# Sheet1.net
KiCad netlist of a schematic drawn in Altium Designer
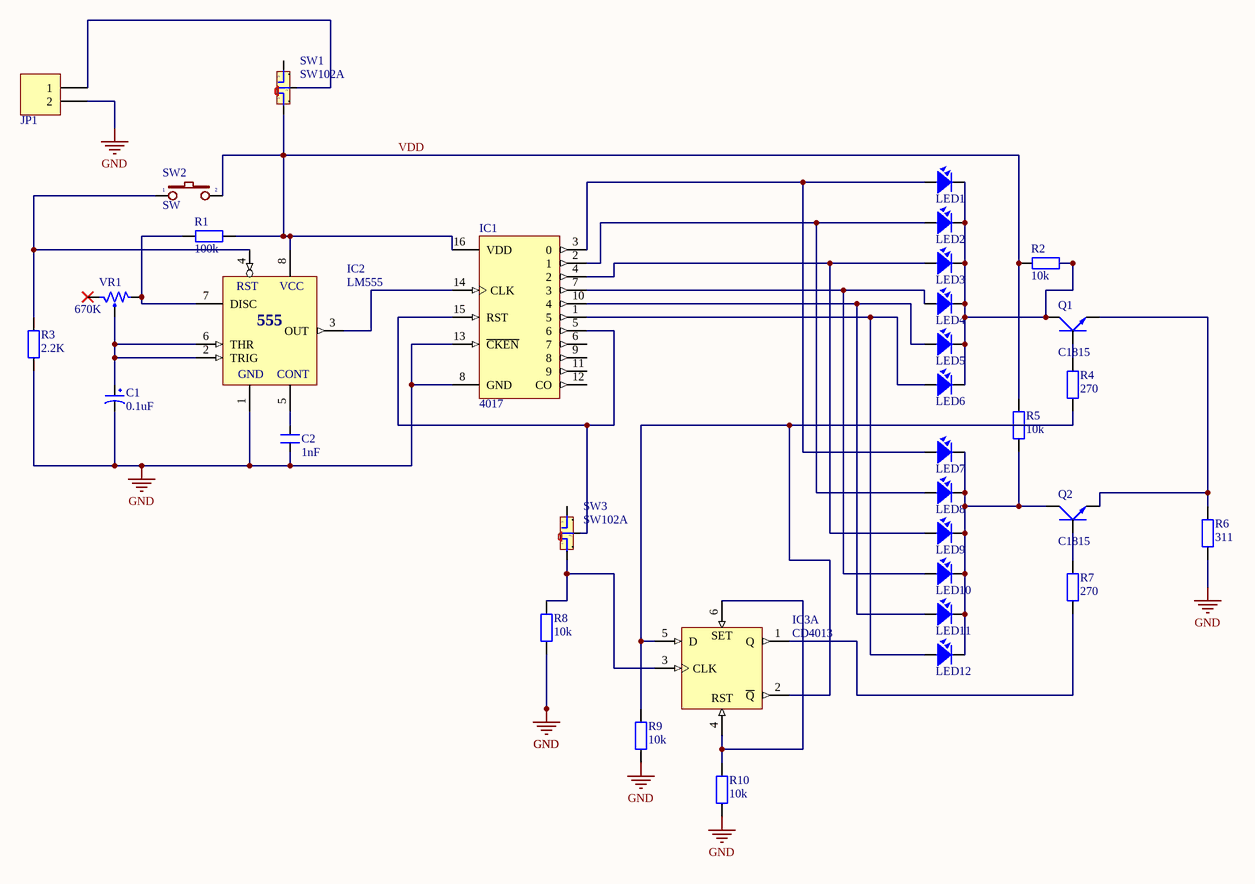
[diagram p0: Sheet1.SchDoc]

(export (version "E")
  (design (tool "Eeschema 10.0.6"))
  (components
    (comp (ref "C1")
      (value "0.1uF")
      (footprint "CP1/2")
      (description "Cap P  0,1uF < 22uF , 16 - 50V")
      (libsource (lib "syhaunguyen") (part "CP1"))
    )
    (comp (ref "C2")
      (value "1nF")
      (footprint "CN1.5")
      (description "Cap np 682pF => 104pF")
      (libsource (lib "syhaunguyen") (part "CN1.5"))
    )
    (comp (ref "IC1")
      (value "4017")
      (footprint "Dip16/w0.3")
      (description "Decade Counter/Divider with 10 Decoded Outputs")
      (fields (field (name "DESIGNED BY") "VanDungEvn"))
      (libsource (lib "My library altium") (part "4017"))
    )
    (comp (ref "IC2")
      (value "LM555")
      (footprint "DIP8/W0.3")
      (description "Timer")
      (libsource (lib "My library altium") (part "LM555"))
    )
    (comp (ref "IC3")
      (value "CD4013")
      (footprint "DIP14/W0.3")
      (description "Dual D-Type Flip-Flop")
      (fields (field (name "CREAT BY") "VanDungEvn@Gmail.com"))
      (libsource (lib "syhaunguyen") (part "CD4013B"))
    )
    (comp (ref "JP1")
      (value "Header 2_1")
      (footprint "HED2")
      (description "Header, 2-Pin")
      (fields (field (name "MANUFACTURER") "Generic Components"))
      (libsource (lib "syhaunguyen") (part "Header 2_1"))
    )
    (comp (ref "LED1")
      (value "LED")
      (footprint "LED-5-RED")
      (description "LED Single colour Green and Red")
      (libsource (lib "syhaunguyen") (part "LED"))
    )
    (comp (ref "LED2")
      (value "LED")
      (footprint "LED-5-RED")
      (description "LED Single colour Green and Red")
      (libsource (lib "syhaunguyen") (part "LED"))
    )
    (comp (ref "LED3")
      (value "LED")
      (footprint "LED-5-RED")
      (description "LED Single colour Green and Red")
      (libsource (lib "syhaunguyen") (part "LED"))
    )
    (comp (ref "LED4")
      (value "LED")
      (footprint "LED-5-RED")
      (description "LED Single colour Green and Red")
      (libsource (lib "syhaunguyen") (part "LED"))
    )
    (comp (ref "LED5")
      (value "LED")
      (footprint "LED-5-RED")
      (description "LED Single colour Green and Red")
      (libsource (lib "syhaunguyen") (part "LED"))
    )
    (comp (ref "LED6")
      (value "LED")
      (footprint "LED-5-RED")
      (description "LED Single colour Green and Red")
      (libsource (lib "syhaunguyen") (part "LED"))
    )
    (comp (ref "LED7")
      (value "LED")
      (footprint "LED-5-RED")
      (description "LED Single colour Green and Red")
      (libsource (lib "syhaunguyen") (part "LED"))
    )
    (comp (ref "LED8")
      (value "LED")
      (footprint "LED-5-RED")
      (description "LED Single colour Green and Red")
      (libsource (lib "syhaunguyen") (part "LED"))
    )
    (comp (ref "LED9")
      (value "LED")
      (footprint "LED-5-RED")
      (description "LED Single colour Green and Red")
      (libsource (lib "syhaunguyen") (part "LED"))
    )
    (comp (ref "LED10")
      (value "LED")
      (footprint "LED-5-RED")
      (description "LED Single colour Green and Red")
      (libsource (lib "syhaunguyen") (part "LED"))
    )
    (comp (ref "LED11")
      (value "LED")
      (footprint "LED-5-RED")
      (description "LED Single colour Green and Red")
      (libsource (lib "syhaunguyen") (part "LED"))
    )
    (comp (ref "LED12")
      (value "LED")
      (footprint "LED-5-RED")
      (description "LED Single colour Green and Red")
      (libsource (lib "syhaunguyen") (part "LED"))
    )
    (comp (ref "Q1")
      (value "C1815")
      (footprint "QTO-92")
      (description "NPN 600mW, ECB")
      (libsource (lib "syhaunguyen") (part "C1815"))
    )
    (comp (ref "Q2")
      (value "C1815")
      (footprint "QTO-92")
      (description "NPN 600mW, ECB")
      (libsource (lib "syhaunguyen") (part "C1815"))
    )
    (comp (ref "R1")
      (value "100k")
      (footprint "R1/4W")
      (description "Resistor 1/4W")
      (libsource (lib "syhaunguyen") (part "R1/4W"))
    )
    (comp (ref "R2")
      (value "10k")
      (footprint "R1/4W")
      (description "Resistor 1/4W")
      (libsource (lib "syhaunguyen") (part "R1/4W"))
    )
    (comp (ref "R3")
      (value "2.2K")
      (footprint "R1/4W")
      (description "Resistor 1/4W")
      (libsource (lib "syhaunguyen") (part "R1/4W"))
    )
    (comp (ref "R4")
      (value "270")
      (footprint "R1/4W")
      (description "Resistor 1/4W")
      (libsource (lib "syhaunguyen") (part "R1/4W"))
    )
    (comp (ref "R5")
      (value "10k")
      (footprint "R1/4W")
      (description "Resistor 1/4W")
      (libsource (lib "syhaunguyen") (part "R1/4W"))
    )
    (comp (ref "R6")
      (value "311")
      (footprint "R1/4W")
      (description "Resistor 1/4W")
      (libsource (lib "syhaunguyen") (part "R1/4W"))
    )
    (comp (ref "R7")
      (value "270")
      (footprint "R1/4W")
      (description "Resistor 1/4W")
      (libsource (lib "syhaunguyen") (part "R1/4W"))
    )
    (comp (ref "R8")
      (value "10k")
      (footprint "R1/4W")
      (description "Resistor 1/4W")
      (libsource (lib "syhaunguyen") (part "R1/4W"))
    )
    (comp (ref "R9")
      (value "10k")
      (footprint "R1/4W")
      (description "Resistor 1/4W")
      (libsource (lib "syhaunguyen") (part "R1/4W"))
    )
    (comp (ref "R10")
      (value "10k")
      (footprint "R1/4W")
      (description "Resistor 1/4W")
      (libsource (lib "syhaunguyen") (part "R1/4W"))
    )
    (comp (ref "SW1")
      (value "SW102A")
      (footprint "SW102")
      (description "Switch 102 on Broad")
      (libsource (lib "My library altium") (part "SW102A"))
    )
    (comp (ref "SW2")
      (value "SW")
      (footprint "SW2")
      (description "Switch button 2 pin")
      (libsource (lib "syhaunguyen") (part "SW2"))
    )
    (comp (ref "SW3")
      (value "SW102A")
      (footprint "SW102")
      (description "Switch 102 on Broad")
      (libsource (lib "My library altium") (part "SW102A"))
    )
    (comp (ref "VR1")
      (value "670K")
      (footprint "VR")
      (description "Var Resistor")
      (libsource (lib "syhaunguyen") (part "VR1"))
    )
  )
  (nets
    (net (code "1") (name "GND") (class "Default")
      (node (ref "C1") (pin "2") (pinfunction "2_2") (pintype "passive"))
      (node (ref "C2") (pin "1") (pinfunction "1_1") (pintype "passive"))
      (node (ref "IC1") (pin "13") (pinfunction "~{CKEN}_13") (pintype "input"))
      (node (ref "IC1") (pin "8") (pinfunction "GND_8") (pintype "power_in"))
      (node (ref "IC2") (pin "1") (pinfunction "GND_1") (pintype "power_in"))
      (node (ref "IC3") (pin "7") (pinfunction "GND_7") (pintype "power_in"))
      (node (ref "JP1") (pin "2") (pinfunction "2_2") (pintype "passive"))
      (node (ref "R10") (pin "1") (pinfunction "1_1") (pintype "passive"))
      (node (ref "R3") (pin "1") (pinfunction "1_1") (pintype "passive"))
      (node (ref "R6") (pin "2") (pinfunction "2_2") (pintype "passive"))
      (node (ref "R8") (pin "2") (pinfunction "2_2") (pintype "passive"))
      (node (ref "R9") (pin "1") (pinfunction "1_1") (pintype "passive"))
    )
    (net (code "2") (name "Net-(IC1-0)") (class "Default")
      (node (ref "IC1") (pin "3") (pinfunction "0_3") (pintype "output"))
      (node (ref "LED1") (pin "1") (pinfunction "1_1") (pintype "passive"))
      (node (ref "LED7") (pin "1") (pinfunction "1_1") (pintype "passive"))
    )
    (net (code "3") (name "Net-(IC1-1)") (class "Default")
      (node (ref "IC1") (pin "2") (pinfunction "1_2") (pintype "output"))
      (node (ref "LED2") (pin "1") (pinfunction "1_1") (pintype "passive"))
      (node (ref "LED8") (pin "1") (pinfunction "1_1") (pintype "passive"))
    )
    (net (code "4") (name "Net-(IC1-2)") (class "Default")
      (node (ref "IC1") (pin "4") (pinfunction "2_4") (pintype "output"))
      (node (ref "LED3") (pin "1") (pinfunction "1_1") (pintype "passive"))
      (node (ref "LED9") (pin "1") (pinfunction "1_1") (pintype "passive"))
    )
    (net (code "5") (name "Net-(IC1-3)") (class "Default")
      (node (ref "IC1") (pin "7") (pinfunction "3_7") (pintype "output"))
      (node (ref "LED10") (pin "1") (pinfunction "1_1") (pintype "passive"))
      (node (ref "LED4") (pin "1") (pinfunction "1_1") (pintype "passive"))
    )
    (net (code "6") (name "Net-(IC1-4)") (class "Default")
      (node (ref "IC1") (pin "10") (pinfunction "4_10") (pintype "output"))
      (node (ref "LED11") (pin "1") (pinfunction "1_1") (pintype "passive"))
      (node (ref "LED5") (pin "1") (pinfunction "1_1") (pintype "passive"))
    )
    (net (code "7") (name "Net-(IC1-5)") (class "Default")
      (node (ref "IC1") (pin "1") (pinfunction "5_1") (pintype "output"))
      (node (ref "LED12") (pin "1") (pinfunction "1_1") (pintype "passive"))
      (node (ref "LED6") (pin "1") (pinfunction "1_1") (pintype "passive"))
    )
    (net (code "8") (name "Net-(IC1-6)") (class "Default")
      (node (ref "IC1") (pin "15") (pinfunction "RST_15") (pintype "input"))
      (node (ref "IC1") (pin "5") (pinfunction "6_5") (pintype "output"))
      (node (ref "SW3") (pin "2") (pinfunction "2_2") (pintype "passive"))
    )
    (net (code "9") (name "Net-(IC1-CLK)") (class "Default")
      (node (ref "IC1") (pin "14") (pinfunction "CLK_14") (pintype "input"))
      (node (ref "IC2") (pin "3") (pinfunction "OUT_3") (pintype "output"))
    )
    (net (code "10") (name "Net-(IC2-CONT)") (class "Default")
      (node (ref "C2") (pin "2") (pinfunction "2_2") (pintype "passive"))
      (node (ref "IC2") (pin "5") (pinfunction "CONT_5") (pintype "passive"))
    )
    (net (code "11") (name "Net-(IC2-DISC)") (class "Default")
      (node (ref "IC2") (pin "7") (pinfunction "DISC_7") (pintype "open_collector"))
      (node (ref "R1") (pin "2") (pinfunction "2_2") (pintype "passive"))
      (node (ref "VR1") (pin "1") (pinfunction "1_1") (pintype "passive"))
    )
    (net (code "12") (name "Net-(IC2-RST)") (class "Default")
      (node (ref "IC2") (pin "4") (pinfunction "RST_4") (pintype "input"))
      (node (ref "R3") (pin "2") (pinfunction "2_2") (pintype "passive"))
      (node (ref "SW2") (pin "1") (pinfunction "1_1") (pintype "passive"))
    )
    (net (code "13") (name "Net-(IC2-THR)") (class "Default")
      (node (ref "C1") (pin "1") (pinfunction "1_1") (pintype "passive"))
      (node (ref "IC2") (pin "2") (pinfunction "TRIG_2") (pintype "input"))
      (node (ref "IC2") (pin "6") (pinfunction "THR_6") (pintype "input"))
      (node (ref "VR1") (pin "2") (pinfunction "2_2") (pintype "passive"))
    )
    (net (code "14") (name "Net-(IC3A-CLK)") (class "Default")
      (node (ref "IC3") (pin "3") (pinfunction "CLK_3") (pintype "input"))
      (node (ref "R8") (pin "1") (pinfunction "1_1") (pintype "passive"))
      (node (ref "SW3") (pin "1") (pinfunction "1_1") (pintype "passive"))
    )
    (net (code "15") (name "Net-(IC3A-D)") (class "Default")
      (node (ref "IC3") (pin "2") (pinfunction "~{Q}_2") (pintype "output"))
      (node (ref "IC3") (pin "5") (pinfunction "D_5") (pintype "input"))
      (node (ref "R4") (pin "2") (pinfunction "2_2") (pintype "passive"))
      (node (ref "R9") (pin "2") (pinfunction "2_2") (pintype "passive"))
    )
    (net (code "16") (name "Net-(IC3A-Q)") (class "Default")
      (node (ref "IC3") (pin "1") (pinfunction "Q_1") (pintype "output"))
      (node (ref "R7") (pin "1") (pinfunction "1_1") (pintype "passive"))
    )
    (net (code "17") (name "Net-(IC3A-RST)") (class "Default")
      (node (ref "IC3") (pin "4") (pinfunction "RST_4") (pintype "input"))
      (node (ref "IC3") (pin "6") (pinfunction "S_6") (pintype "input"))
      (node (ref "R10") (pin "2") (pinfunction "2_2") (pintype "passive"))
    )
    (net (code "18") (name "Net-(JP1-Pad1)") (class "Default")
      (node (ref "JP1") (pin "1") (pinfunction "1_1") (pintype "passive"))
      (node (ref "SW1") (pin "2") (pinfunction "2_2") (pintype "passive"))
    )
    (net (code "19") (name "Net-(Q1-B)") (class "Default")
      (node (ref "Q1") (pin "3") (pinfunction "B_3") (pintype "passive"))
      (node (ref "R4") (pin "1") (pinfunction "1_1") (pintype "passive"))
    )
    (net (code "20") (name "Net-(Q1-C)") (class "Default")
      (node (ref "LED1") (pin "2") (pinfunction "2_2") (pintype "passive"))
      (node (ref "LED2") (pin "2") (pinfunction "2_2") (pintype "passive"))
      (node (ref "LED3") (pin "2") (pinfunction "2_2") (pintype "passive"))
      (node (ref "LED4") (pin "2") (pinfunction "2_2") (pintype "passive"))
      (node (ref "LED5") (pin "2") (pinfunction "2_2") (pintype "passive"))
      (node (ref "LED6") (pin "2") (pinfunction "2_2") (pintype "passive"))
      (node (ref "Q1") (pin "2") (pinfunction "C_2") (pintype "passive"))
      (node (ref "R2") (pin "1") (pinfunction "1_1") (pintype "passive"))
    )
    (net (code "21") (name "Net-(Q1-E)") (class "Default")
      (node (ref "Q1") (pin "1") (pinfunction "E_1") (pintype "passive"))
      (node (ref "Q2") (pin "1") (pinfunction "E_1") (pintype "passive"))
      (node (ref "R6") (pin "1") (pinfunction "1_1") (pintype "passive"))
    )
    (net (code "22") (name "Net-(Q2-B)") (class "Default")
      (node (ref "Q2") (pin "3") (pinfunction "B_3") (pintype "passive"))
      (node (ref "R7") (pin "2") (pinfunction "2_2") (pintype "passive"))
    )
    (net (code "23") (name "Net-(Q2-C)") (class "Default")
      (node (ref "LED10") (pin "2") (pinfunction "2_2") (pintype "passive"))
      (node (ref "LED11") (pin "2") (pinfunction "2_2") (pintype "passive"))
      (node (ref "LED12") (pin "2") (pinfunction "2_2") (pintype "passive"))
      (node (ref "LED7") (pin "2") (pinfunction "2_2") (pintype "passive"))
      (node (ref "LED8") (pin "2") (pinfunction "2_2") (pintype "passive"))
      (node (ref "LED9") (pin "2") (pinfunction "2_2") (pintype "passive"))
      (node (ref "Q2") (pin "2") (pinfunction "C_2") (pintype "passive"))
      (node (ref "R5") (pin "1") (pinfunction "1_1") (pintype "passive"))
    )
    (net (code "24") (name "VDD") (class "Default")
      (node (ref "IC1") (pin "16") (pinfunction "VDD_16") (pintype "power_in"))
      (node (ref "IC2") (pin "8") (pinfunction "VCC_8") (pintype "power_in"))
      (node (ref "IC3") (pin "14") (pinfunction "VDD_14") (pintype "power_in"))
      (node (ref "R1") (pin "1") (pinfunction "1_1") (pintype "passive"))
      (node (ref "R2") (pin "2") (pinfunction "2_2") (pintype "passive"))
      (node (ref "R5") (pin "2") (pinfunction "2_2") (pintype "passive"))
      (node (ref "SW1") (pin "1") (pinfunction "1_1") (pintype "passive"))
      (node (ref "SW2") (pin "2") (pinfunction "2_2") (pintype "passive"))
    )
    (net (code "25") (name "unconnected-(IC1-7-Pad6)") (class "Default")
      (node (ref "IC1") (pin "6") (pinfunction "7_6") (pintype "output"))
    )
    (net (code "26") (name "unconnected-(IC1-8-Pad9)") (class "Default")
      (node (ref "IC1") (pin "9") (pinfunction "8_9") (pintype "output"))
    )
    (net (code "27") (name "unconnected-(IC1-9-Pad11)") (class "Default")
      (node (ref "IC1") (pin "11") (pinfunction "9_11") (pintype "output"))
    )
    (net (code "28") (name "unconnected-(IC1-CO-Pad12)") (class "Default")
      (node (ref "IC1") (pin "12") (pinfunction "CO_12") (pintype "output"))
    )
    (net (code "29") (name "unconnected-(SW1-Pad3)") (class "Default")
      (node (ref "SW1") (pin "3") (pinfunction "3_3") (pintype "passive"))
    )
    (net (code "30") (name "unconnected-(SW1-Pad4)") (class "Default")
      (node (ref "SW1") (pin "4") (pinfunction "4_4") (pintype "passive"))
    )
    (net (code "31") (name "unconnected-(SW1-Pad5)") (class "Default")
      (node (ref "SW1") (pin "5") (pinfunction "5_5") (pintype "passive"))
    )
    (net (code "32") (name "unconnected-(SW3-Pad3)") (class "Default")
      (node (ref "SW3") (pin "3") (pinfunction "3_3") (pintype "passive"))
    )
    (net (code "33") (name "unconnected-(SW3-Pad4)") (class "Default")
      (node (ref "SW3") (pin "4") (pinfunction "4_4") (pintype "passive"))
    )
    (net (code "34") (name "unconnected-(SW3-Pad5)") (class "Default")
      (node (ref "SW3") (pin "5") (pinfunction "5_5") (pintype "passive"))
    )
    (net (code "35") (name "unconnected-(VR1-Pad3)") (class "Default")
      (node (ref "VR1") (pin "3") (pinfunction "3_3") (pintype "passive+no_connect"))
    )
  )
)
